# HBridgeControl.net
KiCad netlist of a schematic drawn in Altium Designer
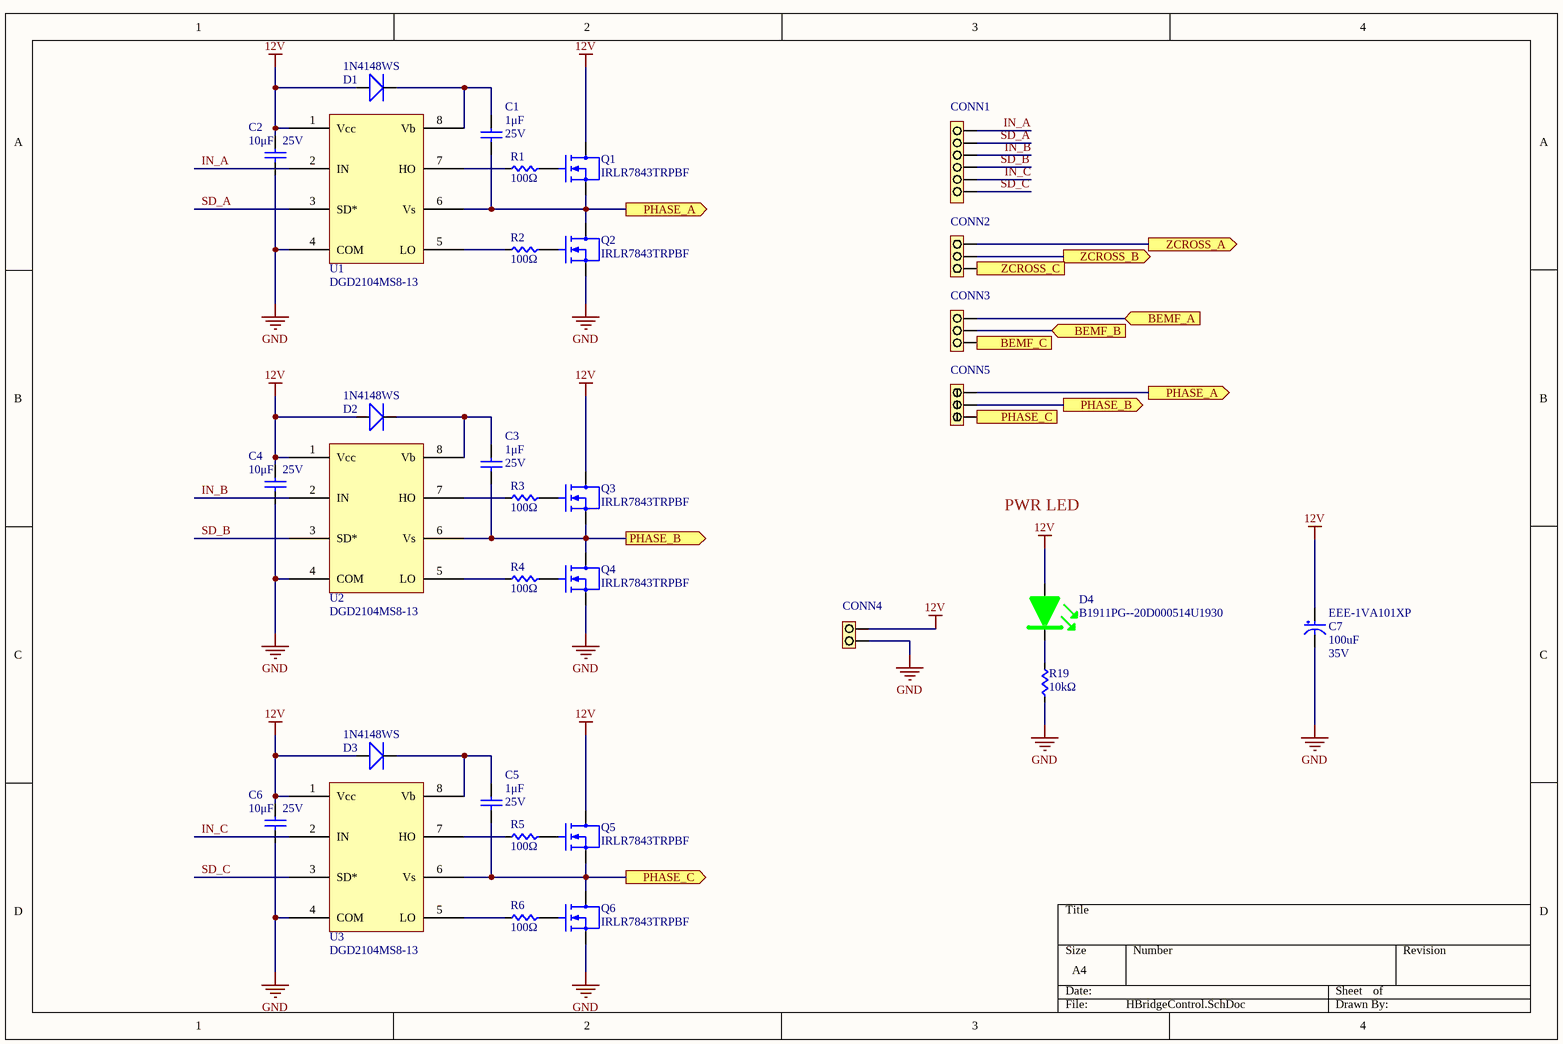
[diagram p0: HBridgeControl.SchDoc]

(export (version "E")
  (design (tool "Eeschema 10.0.6"))
  (components
    (comp (ref "C1")
      (value "1μF")
      (footprint "CAP0603")
      (description "CAP CER 1UF 25V X7R 0603")
      (fields (field (name "VOLTAGE RATING") "25V") (field (name "Comment") "GCM188R71E105KA64D"))
      (libsource (lib "BLDC_Schematic_Library") (part "GCM188R71E105KA64D"))
    )
    (comp (ref "C2")
      (value "10μF")
      (footprint "CAP0603")
      (description "CAP CER 10UF 25V X5R 0603")
      (fields (field (name "VOLTAGE RATING") "25V") (field (name "Comment") "GRM188R61E106MA73J"))
      (libsource (lib "BLDC_Schematic_Library") (part "GRM188R61E106MA73J"))
    )
    (comp (ref "C3")
      (value "1μF")
      (footprint "CAP0603")
      (description "CAP CER 1UF 25V X7R 0603")
      (fields (field (name "VOLTAGE RATING") "25V") (field (name "Comment") "GCM188R71E105KA64D"))
      (libsource (lib "BLDC_Schematic_Library") (part "GCM188R71E105KA64D"))
    )
    (comp (ref "C4")
      (value "10μF")
      (footprint "CAP0603")
      (description "CAP CER 10UF 25V X5R 0603")
      (fields (field (name "VOLTAGE RATING") "25V") (field (name "Comment") "GRM188R61E106MA73J"))
      (libsource (lib "BLDC_Schematic_Library") (part "GRM188R61E106MA73J"))
    )
    (comp (ref "C5")
      (value "1μF")
      (footprint "CAP0603")
      (description "CAP CER 1UF 25V X7R 0603")
      (fields (field (name "VOLTAGE RATING") "25V") (field (name "Comment") "GCM188R71E105KA64D"))
      (libsource (lib "BLDC_Schematic_Library") (part "GCM188R71E105KA64D"))
    )
    (comp (ref "C6")
      (value "10μF")
      (footprint "CAP0603")
      (description "CAP CER 10UF 25V X5R 0603")
      (fields (field (name "VOLTAGE RATING") "25V") (field (name "Comment") "GRM188R61E106MA73J"))
      (libsource (lib "BLDC_Schematic_Library") (part "GRM188R61E106MA73J"))
    )
    (comp (ref "C7")
      (value "EEE-1VA101XP")
      (footprint "SMD")
      (description "CAP ALUM 100UF 20% 35V SMD")
      (fields (field (name "CAPACITANCE") "100uF") (field (name "VOLTAGE RATING") "35V"))
      (libsource (lib "BLDC_Schematic_Library") (part "EEE-1VA101XP"))
    )
    (comp (ref "CONN1")
      (value "MALE6PINCONN")
      (footprint "6POS HEADER")
      (libsource (lib "BLDC_Schematic_Library") (part "MALE6PINCONN"))
    )
    (comp (ref "CONN2")
      (value "MALE3PINCONN")
      (footprint "3POS HEADER")
      (libsource (lib "BLDC_Schematic_Library") (part "MALE3PINCONN"))
    )
    (comp (ref "CONN3")
      (value "MALE3PINCONN")
      (footprint "3POS HEADER")
      (libsource (lib "BLDC_Schematic_Library") (part "MALE3PINCONN"))
    )
    (comp (ref "CONN4")
      (value "MALE2PINCONN")
      (footprint "2POS HEADER")
      (libsource (lib "BLDC_Schematic_Library") (part "MALE2PINCONN"))
    )
    (comp (ref "CONN5")
      (value "SCREW3PINCONN")
      (footprint "SCREW3POSCONN")
      (libsource (lib "BLDC_Schematic_Library") (part "SCREW3PINCONN"))
    )
    (comp (ref "D1")
      (value "1N4148WS")
      (footprint "SOD_323")
      (description "DIODE GEN PURP 75V 150MA SOD323F")
      (fields (field (name "MANUFACTURER") "Onsemi"))
      (libsource (lib "BLDC_Schematic_Library") (part "1N4148WS"))
    )
    (comp (ref "D2")
      (value "1N4148WS")
      (footprint "SOD_323")
      (description "DIODE GEN PURP 75V 150MA SOD323F")
      (fields (field (name "MANUFACTURER") "Onsemi"))
      (libsource (lib "BLDC_Schematic_Library") (part "1N4148WS"))
    )
    (comp (ref "D3")
      (value "1N4148WS")
      (footprint "SOD_323")
      (description "DIODE GEN PURP 75V 150MA SOD323F")
      (fields (field (name "MANUFACTURER") "Onsemi"))
      (libsource (lib "BLDC_Schematic_Library") (part "1N4148WS"))
    )
    (comp (ref "D4")
      (value "B1911PG--20D000514U1930")
      (footprint "LED0603")
      (description "LED GREEN DIFFUSED 0603 SMD")
      (libsource (lib "BLDC_Schematic_Library") (part "B1911PG--20D000514U1930"))
    )
    (comp (ref "Q1")
      (value "IRLR7843TRPBF")
      (footprint "TO-252AA (DPAK)")
      (description "N-Channel 30 V 161A (Tc) 140W (Tc) Surface Mount TO-252AA (DPAK)")
      (fields (field (name "MANUFACTURER") "Infineon Technologies"))
      (libsource (lib "BLDC_Schematic_Library") (part "IRLR7843TRPBF"))
    )
    (comp (ref "Q2")
      (value "IRLR7843TRPBF")
      (footprint "TO-252AA (DPAK)")
      (description "N-Channel 30 V 161A (Tc) 140W (Tc) Surface Mount TO-252AA (DPAK)")
      (fields (field (name "MANUFACTURER") "Infineon Technologies"))
      (libsource (lib "BLDC_Schematic_Library") (part "IRLR7843TRPBF"))
    )
    (comp (ref "Q3")
      (value "IRLR7843TRPBF")
      (footprint "TO-252AA (DPAK)")
      (description "N-Channel 30 V 161A (Tc) 140W (Tc) Surface Mount TO-252AA (DPAK)")
      (fields (field (name "MANUFACTURER") "Infineon Technologies"))
      (libsource (lib "BLDC_Schematic_Library") (part "IRLR7843TRPBF"))
    )
    (comp (ref "Q4")
      (value "IRLR7843TRPBF")
      (footprint "TO-252AA (DPAK)")
      (description "N-Channel 30 V 161A (Tc) 140W (Tc) Surface Mount TO-252AA (DPAK)")
      (fields (field (name "MANUFACTURER") "Infineon Technologies"))
      (libsource (lib "BLDC_Schematic_Library") (part "IRLR7843TRPBF"))
    )
    (comp (ref "Q5")
      (value "IRLR7843TRPBF")
      (footprint "TO-252AA (DPAK)")
      (description "N-Channel 30 V 161A (Tc) 140W (Tc) Surface Mount TO-252AA (DPAK)")
      (fields (field (name "MANUFACTURER") "Infineon Technologies"))
      (libsource (lib "BLDC_Schematic_Library") (part "IRLR7843TRPBF"))
    )
    (comp (ref "Q6")
      (value "IRLR7843TRPBF")
      (footprint "TO-252AA (DPAK)")
      (description "N-Channel 30 V 161A (Tc) 140W (Tc) Surface Mount TO-252AA (DPAK)")
      (fields (field (name "MANUFACTURER") "Infineon Technologies"))
      (libsource (lib "BLDC_Schematic_Library") (part "IRLR7843TRPBF"))
    )
    (comp (ref "R1")
      (value "100Ω")
      (footprint "RES0603")
      (description "RES 100 OHM 1% 1/10W 0603")
      (fields (field (name "Comment") "RC0402JR-0710KL_1"))
      (libsource (lib "BLDC_Schematic_Library") (part "RC0402JR-0710KL_1"))
    )
    (comp (ref "R2")
      (value "100Ω")
      (footprint "RES0603")
      (description "RES 100 OHM 1% 1/10W 0603")
      (fields (field (name "Comment") "RC0402JR-0710KL_1"))
      (libsource (lib "BLDC_Schematic_Library") (part "RC0402JR-0710KL_1"))
    )
    (comp (ref "R3")
      (value "100Ω")
      (footprint "RES0603")
      (description "RES 100 OHM 1% 1/10W 0603")
      (fields (field (name "Comment") "RC0402JR-0710KL_1"))
      (libsource (lib "BLDC_Schematic_Library") (part "RC0402JR-0710KL_1"))
    )
    (comp (ref "R4")
      (value "100Ω")
      (footprint "RES0603")
      (description "RES 100 OHM 1% 1/10W 0603")
      (fields (field (name "Comment") "RC0402JR-0710KL_1"))
      (libsource (lib "BLDC_Schematic_Library") (part "RC0402JR-0710KL_1"))
    )
    (comp (ref "R5")
      (value "100Ω")
      (footprint "RES0603")
      (description "RES 100 OHM 1% 1/10W 0603")
      (fields (field (name "Comment") "RC0402JR-0710KL_1"))
      (libsource (lib "BLDC_Schematic_Library") (part "RC0402JR-0710KL_1"))
    )
    (comp (ref "R6")
      (value "100Ω")
      (footprint "RES0603")
      (description "RES 100 OHM 1% 1/10W 0603")
      (fields (field (name "Comment") "RC0402JR-0710KL_1"))
      (libsource (lib "BLDC_Schematic_Library") (part "RC0402JR-0710KL_1"))
    )
    (comp (ref "R19")
      (value "10kΩ")
      (footprint "RES0402")
      (description "RES 10K OHM 5% 1/16W 0402")
      (fields (field (name "Comment") "RC0402JR-0710KL"))
      (libsource (lib "BLDC_Schematic_Library") (part "RC0402JR-0710KL"))
    )
    (comp (ref "U1")
      (value "DGD2104MS8-13")
      (footprint "8SO")
      (description "IC GATE DRVR HALF-BRIDGE 8-SO")
      (fields (field (name "MANUFACTURER") "Diodes Incorporated"))
      (libsource (lib "BLDC_Schematic_Library") (part "DGD2104MS8-13"))
    )
    (comp (ref "U2")
      (value "DGD2104MS8-13")
      (footprint "8SO")
      (description "IC GATE DRVR HALF-BRIDGE 8-SO")
      (fields (field (name "MANUFACTURER") "Diodes Incorporated"))
      (libsource (lib "BLDC_Schematic_Library") (part "DGD2104MS8-13"))
    )
    (comp (ref "U3")
      (value "DGD2104MS8-13")
      (footprint "8SO")
      (description "IC GATE DRVR HALF-BRIDGE 8-SO")
      (fields (field (name "MANUFACTURER") "Diodes Incorporated"))
      (libsource (lib "BLDC_Schematic_Library") (part "DGD2104MS8-13"))
    )
  )
  (nets
    (net (code "1") (name "/BEMF_A") (class "Default")
      (node (ref "CONN3") (pin "1") (pinfunction "1_1") (pintype "passive"))
    )
    (net (code "2") (name "/BEMF_B") (class "Default")
      (node (ref "CONN3") (pin "2") (pinfunction "2_2") (pintype "passive"))
    )
    (net (code "3") (name "/BEMF_C") (class "Default")
      (node (ref "CONN3") (pin "3") (pinfunction "3_3") (pintype "passive"))
    )
    (net (code "4") (name "/IN_A") (class "Default")
      (node (ref "CONN1") (pin "1") (pinfunction "1_1") (pintype "passive"))
      (node (ref "U1") (pin "2") (pinfunction "IN_2") (pintype "passive"))
    )
    (net (code "5") (name "/IN_B") (class "Default")
      (node (ref "CONN1") (pin "3") (pinfunction "3_3") (pintype "passive"))
      (node (ref "U2") (pin "2") (pinfunction "IN_2") (pintype "passive"))
    )
    (net (code "6") (name "/IN_C") (class "Default")
      (node (ref "CONN1") (pin "5") (pinfunction "5_5") (pintype "passive"))
      (node (ref "U3") (pin "2") (pinfunction "IN_2") (pintype "passive"))
    )
    (net (code "7") (name "/PHASE_A") (class "Default")
      (node (ref "C1") (pin "2") (pinfunction "2_2") (pintype "passive"))
      (node (ref "CONN5") (pin "1") (pinfunction "1_1") (pintype "passive"))
      (node (ref "Q1") (pin "3") (pinfunction "3_3") (pintype "passive"))
      (node (ref "Q2") (pin "2") (pinfunction "2_2") (pintype "passive"))
      (node (ref "U1") (pin "6") (pinfunction "Vs_6") (pintype "passive"))
    )
    (net (code "8") (name "/PHASE_B") (class "Default")
      (node (ref "C3") (pin "2") (pinfunction "2_2") (pintype "passive"))
      (node (ref "CONN5") (pin "2") (pinfunction "2_2") (pintype "passive"))
      (node (ref "Q3") (pin "3") (pinfunction "3_3") (pintype "passive"))
      (node (ref "Q4") (pin "2") (pinfunction "2_2") (pintype "passive"))
      (node (ref "U2") (pin "6") (pinfunction "Vs_6") (pintype "passive"))
    )
    (net (code "9") (name "/PHASE_C") (class "Default")
      (node (ref "C5") (pin "2") (pinfunction "2_2") (pintype "passive"))
      (node (ref "CONN5") (pin "3") (pinfunction "3_3") (pintype "passive"))
      (node (ref "Q5") (pin "3") (pinfunction "3_3") (pintype "passive"))
      (node (ref "Q6") (pin "2") (pinfunction "2_2") (pintype "passive"))
      (node (ref "U3") (pin "6") (pinfunction "Vs_6") (pintype "passive"))
    )
    (net (code "10") (name "/SD_A") (class "Default")
      (node (ref "CONN1") (pin "2") (pinfunction "2_2") (pintype "passive"))
      (node (ref "U1") (pin "3") (pinfunction "SD*_3") (pintype "passive"))
    )
    (net (code "11") (name "/SD_B") (class "Default")
      (node (ref "CONN1") (pin "4") (pinfunction "4_4") (pintype "passive"))
      (node (ref "U2") (pin "3") (pinfunction "SD*_3") (pintype "passive"))
    )
    (net (code "12") (name "/SD_C") (class "Default")
      (node (ref "CONN1") (pin "6") (pinfunction "6_6") (pintype "passive"))
      (node (ref "U3") (pin "3") (pinfunction "SD*_3") (pintype "passive"))
    )
    (net (code "13") (name "/ZCROSS_A") (class "Default")
      (node (ref "CONN2") (pin "1") (pinfunction "1_1") (pintype "passive"))
    )
    (net (code "14") (name "/ZCROSS_B") (class "Default")
      (node (ref "CONN2") (pin "2") (pinfunction "2_2") (pintype "passive"))
    )
    (net (code "15") (name "/ZCROSS_C") (class "Default")
      (node (ref "CONN2") (pin "3") (pinfunction "3_3") (pintype "passive"))
    )
    (net (code "16") (name "12V") (class "Default")
      (node (ref "C2") (pin "1") (pinfunction "1_1") (pintype "passive"))
      (node (ref "C4") (pin "1") (pinfunction "1_1") (pintype "passive"))
      (node (ref "C6") (pin "1") (pinfunction "1_1") (pintype "passive"))
      (node (ref "C7") (pin "1") (pinfunction "1_1") (pintype "passive"))
      (node (ref "CONN4") (pin "1") (pinfunction "1_1") (pintype "passive"))
      (node (ref "D1") (pin "1") (pinfunction "1_1") (pintype "passive"))
      (node (ref "D2") (pin "1") (pinfunction "1_1") (pintype "passive"))
      (node (ref "D3") (pin "1") (pinfunction "1_1") (pintype "passive"))
      (node (ref "D4") (pin "1") (pinfunction "1_1") (pintype "passive"))
      (node (ref "Q1") (pin "2") (pinfunction "2_2") (pintype "passive"))
      (node (ref "Q3") (pin "2") (pinfunction "2_2") (pintype "passive"))
      (node (ref "Q5") (pin "2") (pinfunction "2_2") (pintype "passive"))
      (node (ref "U1") (pin "1") (pinfunction "Vcc_1") (pintype "passive"))
      (node (ref "U2") (pin "1") (pinfunction "Vcc_1") (pintype "passive"))
      (node (ref "U3") (pin "1") (pinfunction "Vcc_1") (pintype "passive"))
    )
    (net (code "17") (name "GND") (class "Default")
      (node (ref "C2") (pin "2") (pinfunction "2_2") (pintype "passive"))
      (node (ref "C4") (pin "2") (pinfunction "2_2") (pintype "passive"))
      (node (ref "C6") (pin "2") (pinfunction "2_2") (pintype "passive"))
      (node (ref "C7") (pin "2") (pinfunction "2_2") (pintype "passive"))
      (node (ref "CONN4") (pin "2") (pinfunction "2_2") (pintype "passive"))
      (node (ref "Q2") (pin "3") (pinfunction "3_3") (pintype "passive"))
      (node (ref "Q4") (pin "3") (pinfunction "3_3") (pintype "passive"))
      (node (ref "Q6") (pin "3") (pinfunction "3_3") (pintype "passive"))
      (node (ref "R19") (pin "2") (pinfunction "2_2") (pintype "passive"))
      (node (ref "U1") (pin "4") (pinfunction "COM_4") (pintype "passive"))
      (node (ref "U2") (pin "4") (pinfunction "COM_4") (pintype "passive"))
      (node (ref "U3") (pin "4") (pinfunction "COM_4") (pintype "passive"))
    )
    (net (code "18") (name "Net-(D4-Pad2)") (class "Default")
      (node (ref "D4") (pin "2") (pinfunction "2_2") (pintype "passive"))
      (node (ref "R19") (pin "1") (pinfunction "1_1") (pintype "passive"))
    )
    (net (code "19") (name "Net-(Q1-Pad1)") (class "Default")
      (node (ref "Q1") (pin "1") (pinfunction "1_1") (pintype "passive"))
      (node (ref "R1") (pin "2") (pinfunction "2_2") (pintype "passive"))
    )
    (net (code "20") (name "Net-(Q2-Pad1)") (class "Default")
      (node (ref "Q2") (pin "1") (pinfunction "1_1") (pintype "passive"))
      (node (ref "R2") (pin "2") (pinfunction "2_2") (pintype "passive"))
    )
    (net (code "21") (name "Net-(Q3-Pad1)") (class "Default")
      (node (ref "Q3") (pin "1") (pinfunction "1_1") (pintype "passive"))
      (node (ref "R3") (pin "2") (pinfunction "2_2") (pintype "passive"))
    )
    (net (code "22") (name "Net-(Q4-Pad1)") (class "Default")
      (node (ref "Q4") (pin "1") (pinfunction "1_1") (pintype "passive"))
      (node (ref "R4") (pin "2") (pinfunction "2_2") (pintype "passive"))
    )
    (net (code "23") (name "Net-(Q5-Pad1)") (class "Default")
      (node (ref "Q5") (pin "1") (pinfunction "1_1") (pintype "passive"))
      (node (ref "R5") (pin "2") (pinfunction "2_2") (pintype "passive"))
    )
    (net (code "24") (name "Net-(Q6-Pad1)") (class "Default")
      (node (ref "Q6") (pin "1") (pinfunction "1_1") (pintype "passive"))
      (node (ref "R6") (pin "2") (pinfunction "2_2") (pintype "passive"))
    )
    (net (code "25") (name "Net-(U1-HO)") (class "Default")
      (node (ref "R1") (pin "1") (pinfunction "1_1") (pintype "passive"))
      (node (ref "U1") (pin "7") (pinfunction "HO_7") (pintype "passive"))
    )
    (net (code "26") (name "Net-(U1-LO)") (class "Default")
      (node (ref "R2") (pin "1") (pinfunction "1_1") (pintype "passive"))
      (node (ref "U1") (pin "5") (pinfunction "LO_5") (pintype "passive"))
    )
    (net (code "27") (name "Net-(U1-Vb)") (class "Default")
      (node (ref "C1") (pin "1") (pinfunction "1_1") (pintype "passive"))
      (node (ref "D1") (pin "2") (pinfunction "2_2") (pintype "passive"))
      (node (ref "U1") (pin "8") (pinfunction "Vb_8") (pintype "passive"))
    )
    (net (code "28") (name "Net-(U2-HO)") (class "Default")
      (node (ref "R3") (pin "1") (pinfunction "1_1") (pintype "passive"))
      (node (ref "U2") (pin "7") (pinfunction "HO_7") (pintype "passive"))
    )
    (net (code "29") (name "Net-(U2-LO)") (class "Default")
      (node (ref "R4") (pin "1") (pinfunction "1_1") (pintype "passive"))
      (node (ref "U2") (pin "5") (pinfunction "LO_5") (pintype "passive"))
    )
    (net (code "30") (name "Net-(U2-Vb)") (class "Default")
      (node (ref "C3") (pin "1") (pinfunction "1_1") (pintype "passive"))
      (node (ref "D2") (pin "2") (pinfunction "2_2") (pintype "passive"))
      (node (ref "U2") (pin "8") (pinfunction "Vb_8") (pintype "passive"))
    )
    (net (code "31") (name "Net-(U3-HO)") (class "Default")
      (node (ref "R5") (pin "1") (pinfunction "1_1") (pintype "passive"))
      (node (ref "U3") (pin "7") (pinfunction "HO_7") (pintype "passive"))
    )
    (net (code "32") (name "Net-(U3-LO)") (class "Default")
      (node (ref "R6") (pin "1") (pinfunction "1_1") (pintype "passive"))
      (node (ref "U3") (pin "5") (pinfunction "LO_5") (pintype "passive"))
    )
    (net (code "33") (name "Net-(U3-Vb)") (class "Default")
      (node (ref "C5") (pin "1") (pinfunction "1_1") (pintype "passive"))
      (node (ref "D3") (pin "2") (pinfunction "2_2") (pintype "passive"))
      (node (ref "U3") (pin "8") (pinfunction "Vb_8") (pintype "passive"))
    )
  )
)
